# keyboardController.net
KiCad netlist of a schematic drawn in EAGLE
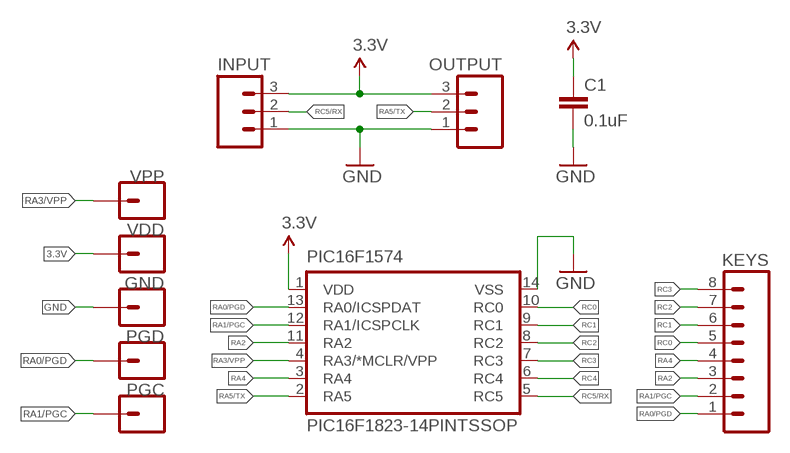
[diagram p0: schematic, sheet 1]

(export (version "E")
  (design (tool "Eeschema 10.0.6"))
  (components
    (comp (ref "C1")
      (value "0.1uF")
      (footprint "eagle-import:0805")
      (libsource (lib "eagle-import") (part "CAP0805"))
    )
    (comp (ref "GND")
      (value "M01PTH")
      (footprint "eagle-import:1X01")
      (libsource (lib "eagle-import") (part "M01PTH"))
    )
    (comp (ref "INPUT")
      (value "M03LONGPADS")
      (footprint "eagle-import:1X03_LONGPADS")
      (libsource (lib "eagle-import") (part "M03LONGPADS"))
    )
    (comp (ref "KEYS")
      (value "M08LONGPADS")
      (footprint "eagle-import:1X08_LONGPADS")
      (libsource (lib "eagle-import") (part "M08LONGPADS"))
    )
    (comp (ref "OUTPUT")
      (value "M03LONGPADS")
      (footprint "eagle-import:1X03_LONGPADS")
      (libsource (lib "eagle-import") (part "M03LONGPADS"))
    )
    (comp (ref "PGC")
      (value "M01PTH")
      (footprint "eagle-import:1X01")
      (libsource (lib "eagle-import") (part "M01PTH"))
    )
    (comp (ref "PGD")
      (value "M01PTH")
      (footprint "eagle-import:1X01")
      (libsource (lib "eagle-import") (part "M01PTH"))
    )
    (comp (ref "PIC16F1574")
      (value "PIC16F1823-14PINTSSOP")
      (footprint "eagle-import:TSSOP14")
      (libsource (lib "eagle-import") (part "PIC16F1823-14PINTSSOP"))
    )
    (comp (ref "VDD")
      (value "M01PTH")
      (footprint "eagle-import:1X01")
      (libsource (lib "eagle-import") (part "M01PTH"))
    )
    (comp (ref "VPP")
      (value "M01PTH")
      (footprint "eagle-import:1X01")
      (libsource (lib "eagle-import") (part "M01PTH"))
    )
  )
  (nets
    (net (code "1") (name "3.3V") (class "Default")
      (node (ref "C1") (pin "1") (pinfunction "1_1") (pintype "passive"))
      (node (ref "INPUT") (pin "3") (pinfunction "3_3") (pintype "passive"))
      (node (ref "OUTPUT") (pin "3") (pinfunction "3_3") (pintype "passive"))
      (node (ref "PIC16F1574") (pin "1") (pinfunction "VDD_1") (pintype "power_in"))
      (node (ref "VDD") (pin "1") (pinfunction "1_1") (pintype "passive"))
    )
    (net (code "2") (name "GND") (class "Default")
      (node (ref "C1") (pin "2") (pinfunction "2_2") (pintype "passive"))
      (node (ref "GND") (pin "1") (pinfunction "1_1") (pintype "passive"))
      (node (ref "INPUT") (pin "1") (pinfunction "1_1") (pintype "passive"))
      (node (ref "OUTPUT") (pin "1") (pinfunction "1_1") (pintype "passive"))
      (node (ref "PIC16F1574") (pin "14") (pinfunction "VSS_14") (pintype "power_in"))
    )
    (net (code "3") (name "RA0{slash}PGD") (class "Default")
      (node (ref "KEYS") (pin "1") (pinfunction "1_1") (pintype "passive"))
      (node (ref "PGD") (pin "1") (pinfunction "1_1") (pintype "passive"))
      (node (ref "PIC16F1574") (pin "13") (pinfunction "RA0/ICSPDAT_13") (pintype "bidirectional"))
    )
    (net (code "4") (name "RA1{slash}PGC") (class "Default")
      (node (ref "KEYS") (pin "2") (pinfunction "2_2") (pintype "passive"))
      (node (ref "PGC") (pin "1") (pinfunction "1_1") (pintype "passive"))
      (node (ref "PIC16F1574") (pin "12") (pinfunction "RA1/ICSPCLK_12") (pintype "bidirectional"))
    )
    (net (code "5") (name "RA2") (class "Default")
      (node (ref "KEYS") (pin "3") (pinfunction "3_3") (pintype "passive"))
      (node (ref "PIC16F1574") (pin "11") (pinfunction "RA2_11") (pintype "bidirectional"))
    )
    (net (code "6") (name "RA3{slash}VPP") (class "Default")
      (node (ref "PIC16F1574") (pin "4") (pinfunction "RA3/*MCLR/VPP_4") (pintype "input"))
      (node (ref "VPP") (pin "1") (pinfunction "1_1") (pintype "passive"))
    )
    (net (code "7") (name "RA4") (class "Default")
      (node (ref "KEYS") (pin "4") (pinfunction "4_4") (pintype "passive"))
      (node (ref "PIC16F1574") (pin "3") (pinfunction "RA4_3") (pintype "bidirectional"))
    )
    (net (code "8") (name "RA5{slash}TX") (class "Default")
      (node (ref "OUTPUT") (pin "2") (pinfunction "2_2") (pintype "passive"))
      (node (ref "PIC16F1574") (pin "2") (pinfunction "RA5_2") (pintype "bidirectional"))
    )
    (net (code "9") (name "RC0") (class "Default")
      (node (ref "KEYS") (pin "5") (pinfunction "5_5") (pintype "passive"))
      (node (ref "PIC16F1574") (pin "10") (pinfunction "RC0_10") (pintype "bidirectional"))
    )
    (net (code "10") (name "RC1") (class "Default")
      (node (ref "KEYS") (pin "6") (pinfunction "6_6") (pintype "passive"))
      (node (ref "PIC16F1574") (pin "9") (pinfunction "RC1_9") (pintype "bidirectional"))
    )
    (net (code "11") (name "RC2") (class "Default")
      (node (ref "KEYS") (pin "7") (pinfunction "7_7") (pintype "passive"))
      (node (ref "PIC16F1574") (pin "8") (pinfunction "RC2_8") (pintype "bidirectional"))
    )
    (net (code "12") (name "RC3") (class "Default")
      (node (ref "KEYS") (pin "8") (pinfunction "8_8") (pintype "passive"))
      (node (ref "PIC16F1574") (pin "7") (pinfunction "RC3_7") (pintype "bidirectional"))
    )
    (net (code "13") (name "RC4") (class "Default")
      (node (ref "PIC16F1574") (pin "6") (pinfunction "RC4_6") (pintype "bidirectional"))
    )
    (net (code "14") (name "RC5{slash}RX") (class "Default")
      (node (ref "INPUT") (pin "2") (pinfunction "2_2") (pintype "passive"))
      (node (ref "PIC16F1574") (pin "5") (pinfunction "RC5_5") (pintype "bidirectional"))
    )
  )
)
